# 01_powersupply.net
KiCad netlist of a schematic drawn in Altium Designer
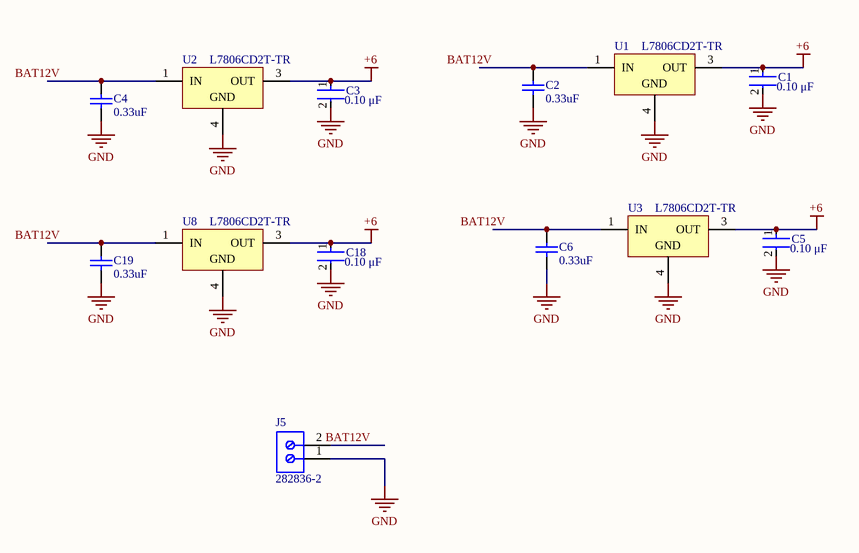
[diagram p0: 01_powersupply.SchDoc]

(export (version "E")
  (design (tool "Eeschema 10.0.6"))
  (components
    (comp (ref "C1")
      (value "C0603_0.1UF")
      (footprint "FP-C0603C-CF-MFG")
      (description "CAP CER 0.1UF 16V X7R 0603")
      (fields
        (field (name "TOLERANCE") "0.2")
        (field (name "CAPACITANCE") "0.10 μF")
        (field (name "MANUFACTURER PART NUMBER") "C0603C104M4RAC7411")
      )
      (libsource (lib "Altium Content Vault") (part "b4654b650e69147ec39a6b967a45e02"))
    )
    (comp (ref "C2")
      (value "0.33uF")
      (footprint "CAPC1608X90X20LL10")
      (description "Chip Capacitor, 0.33 uF, +/- 10%, 50 V, -55 to 125 degC, 0603 (1608 Metric), RoHS, Tape and Reel")
      (fields (field (name "MANUFACTURER") "TDK") (field (name "Comment") "C0603_0.33UF"))
      (libsource (lib "Altium Content Vault") (part "CAP-NP-2"))
    )
    (comp (ref "C3")
      (value "C0603_0.1UF")
      (footprint "FP-C0603C-CF-MFG")
      (description "CAP CER 0.1UF 16V X7R 0603")
      (fields
        (field (name "TOLERANCE") "0.2")
        (field (name "CAPACITANCE") "0.10 μF")
        (field (name "MANUFACTURER PART NUMBER") "C0603C104M4RAC7411")
      )
      (libsource (lib "Altium Content Vault") (part "b4654b650e69147ec39a6b967a45e02"))
    )
    (comp (ref "C4")
      (value "0.33uF")
      (footprint "CAPC1608X90X20LL10")
      (description "Chip Capacitor, 0.33 uF, +/- 10%, 50 V, -55 to 125 degC, 0603 (1608 Metric), RoHS, Tape and Reel")
      (fields (field (name "MANUFACTURER") "TDK") (field (name "Comment") "C0603_0.33UF"))
      (libsource (lib "Altium Content Vault") (part "CAP-NP-2"))
    )
    (comp (ref "C5")
      (value "C0603_0.1UF")
      (footprint "FP-C0603C-CF-MFG")
      (description "CAP CER 0.1UF 16V X7R 0603")
      (fields
        (field (name "TOLERANCE") "0.2")
        (field (name "CAPACITANCE") "0.10 μF")
        (field (name "MANUFACTURER PART NUMBER") "C0603C104M4RAC7411")
      )
      (libsource (lib "Altium Content Vault") (part "b4654b650e69147ec39a6b967a45e02"))
    )
    (comp (ref "C6")
      (value "0.33uF")
      (footprint "CAPC1608X90X20LL10")
      (description "Chip Capacitor, 0.33 uF, +/- 10%, 50 V, -55 to 125 degC, 0603 (1608 Metric), RoHS, Tape and Reel")
      (fields (field (name "MANUFACTURER") "TDK") (field (name "Comment") "C0603_0.33UF"))
      (libsource (lib "Altium Content Vault") (part "CAP-NP-2"))
    )
    (comp (ref "C18")
      (value "C0603_0.1UF")
      (footprint "FP-C0603C-CF-MFG")
      (description "CAP CER 0.1UF 16V X7R 0603")
      (fields
        (field (name "TOLERANCE") "0.2")
        (field (name "CAPACITANCE") "0.10 μF")
        (field (name "MANUFACTURER PART NUMBER") "C0603C104M4RAC7411")
      )
      (libsource (lib "Altium Content Vault") (part "b4654b650e69147ec39a6b967a45e02"))
    )
    (comp (ref "C19")
      (value "0.33uF")
      (footprint "CAPC1608X90X20LL10")
      (description "Chip Capacitor, 0.33 uF, +/- 10%, 50 V, -55 to 125 degC, 0603 (1608 Metric), RoHS, Tape and Reel")
      (fields (field (name "MANUFACTURER") "TDK") (field (name "Comment") "C0603_0.33UF"))
      (libsource (lib "Altium Content Vault") (part "CAP-NP-2"))
    )
    (comp (ref "J5")
      (value "282836-2")
      (footprint "TECO-282836-2_V")
      (description "Female Header, Pitch 5 mm, 1 x 2 Position, Height 10 mm, Tail Length 3.5 mm, Rohs, Bulk")
      (fields (field (name "VOLTAGE") "300V") (field (name "MANUFACTURER") "TE Connectivity"))
      (libsource (lib "Altium Content Vault") (part "CN-1P-F-TB2"))
    )
    (comp (ref "U1")
      (value "L7806CD2T-TR")
      (footprint "TO-263_L")
      (description "Positive Voltage Regulator, 3-Pin D2PAK, Tape and Reel")
      (libsource (lib "Altium Content Vault") (part "PM-REG-L4940-SOT3"))
    )
    (comp (ref "U2")
      (value "L7806CD2T-TR")
      (footprint "TO-263_L")
      (description "Positive Voltage Regulator, 3-Pin D2PAK, Tape and Reel")
      (libsource (lib "Altium Content Vault") (part "PM-REG-L4940-SOT3"))
    )
    (comp (ref "U3")
      (value "L7806CD2T-TR")
      (footprint "TO-263_L")
      (description "Positive Voltage Regulator, 3-Pin D2PAK, Tape and Reel")
      (libsource (lib "Altium Content Vault") (part "PM-REG-L4940-SOT3"))
    )
    (comp (ref "U8")
      (value "L7806CD2T-TR")
      (footprint "TO-263_L")
      (description "Positive Voltage Regulator, 3-Pin D2PAK, Tape and Reel")
      (libsource (lib "Altium Content Vault") (part "PM-REG-L4940-SOT3"))
    )
  )
  (nets
    (net (code "1") (name "+6") (class "Default")
      (node (ref "C1") (pin "1") (pinfunction "1_1") (pintype "passive"))
      (node (ref "C18") (pin "1") (pinfunction "1_1") (pintype "passive"))
      (node (ref "C3") (pin "1") (pinfunction "1_1") (pintype "passive"))
      (node (ref "C5") (pin "1") (pinfunction "1_1") (pintype "passive"))
      (node (ref "U1") (pin "3") (pinfunction "OUT_3") (pintype "power_in"))
      (node (ref "U2") (pin "3") (pinfunction "OUT_3") (pintype "power_in"))
      (node (ref "U3") (pin "3") (pinfunction "OUT_3") (pintype "power_in"))
      (node (ref "U8") (pin "3") (pinfunction "OUT_3") (pintype "power_in"))
    )
    (net (code "2") (name "/BAT12V") (class "Default")
      (node (ref "C19") (pin "2") (pinfunction "2_2") (pintype "passive"))
      (node (ref "C2") (pin "2") (pinfunction "2_2") (pintype "passive"))
      (node (ref "C4") (pin "2") (pinfunction "2_2") (pintype "passive"))
      (node (ref "C6") (pin "2") (pinfunction "2_2") (pintype "passive"))
      (node (ref "J5") (pin "2") (pinfunction "2_2") (pintype "passive"))
      (node (ref "U1") (pin "1") (pinfunction "IN_1") (pintype "power_in"))
      (node (ref "U2") (pin "1") (pinfunction "IN_1") (pintype "power_in"))
      (node (ref "U3") (pin "1") (pinfunction "IN_1") (pintype "power_in"))
      (node (ref "U8") (pin "1") (pinfunction "IN_1") (pintype "power_in"))
    )
    (net (code "3") (name "GND") (class "Default")
      (node (ref "C1") (pin "2") (pinfunction "2_2") (pintype "passive"))
      (node (ref "C18") (pin "2") (pinfunction "2_2") (pintype "passive"))
      (node (ref "C19") (pin "1") (pinfunction "1_1") (pintype "passive"))
      (node (ref "C2") (pin "1") (pinfunction "1_1") (pintype "passive"))
      (node (ref "C3") (pin "2") (pinfunction "2_2") (pintype "passive"))
      (node (ref "C4") (pin "1") (pinfunction "1_1") (pintype "passive"))
      (node (ref "C5") (pin "2") (pinfunction "2_2") (pintype "passive"))
      (node (ref "C6") (pin "1") (pinfunction "1_1") (pintype "passive"))
      (node (ref "J5") (pin "1") (pinfunction "1_1") (pintype "passive"))
      (node (ref "U1") (pin "4") (pinfunction "GND_4") (pintype "power_in"))
      (node (ref "U2") (pin "4") (pinfunction "GND_4") (pintype "power_in"))
      (node (ref "U3") (pin "4") (pinfunction "GND_4") (pintype "power_in"))
      (node (ref "U8") (pin "4") (pinfunction "GND_4") (pintype "power_in"))
    )
  )
)
